# MEGA2560_Rev3e_0.net
KiCad netlist of a schematic drawn in Altium Designer
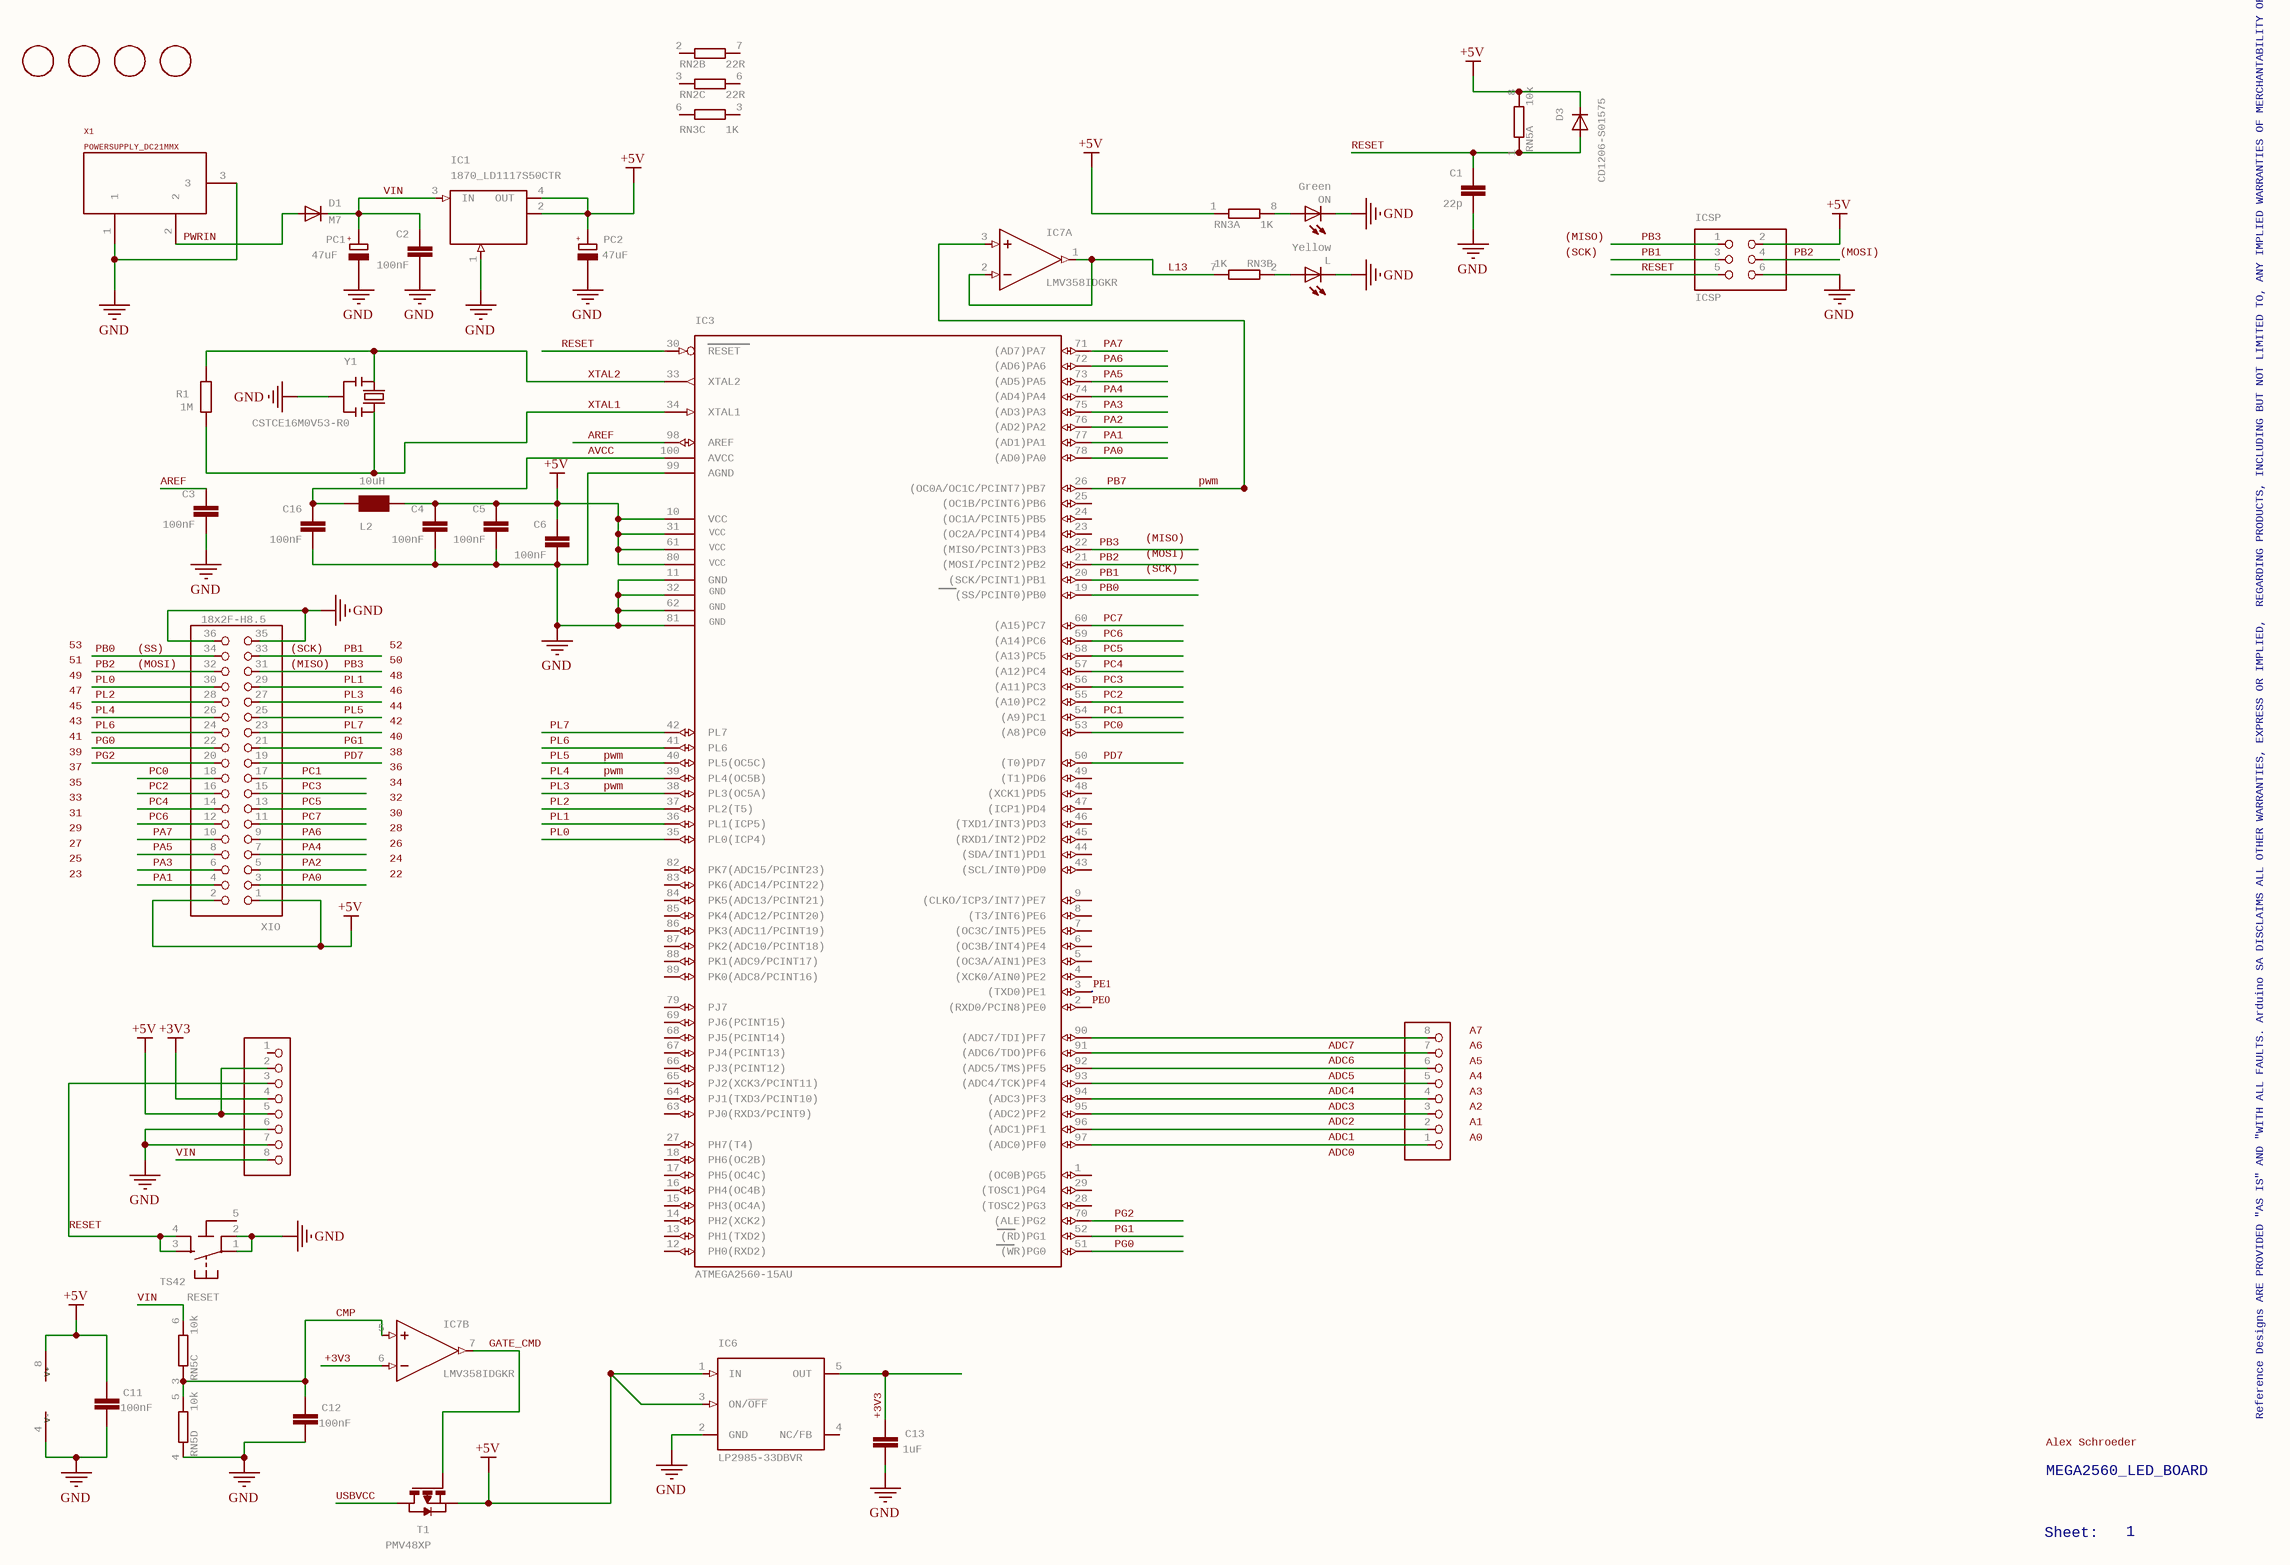
[diagram p0: MEGA2560_Rev3e_0.SchDoc]

(export (version "E")
  (design (tool "Eeschema 10.0.6"))
  (components
    (comp (ref "ADCL")
      (value "FH254-108DF08500V")
      (footprint "1X08")
      (description "Female Connector strip for Arduino bases - 8x1 F V h 8,5 p2,54mm")
      (fields (field (name "LIBRARYNAME") "Connettori"))
      (libsource (lib "Connettori") (part "0058_FH254-108DF08500V"))
    )
    (comp (ref "C1")
      (value "22p")
      (footprint "C0603-ROUND")
      (description "22pF 0603")
      (fields (field (name "PART_NUMBER") "22pF_0603"))
      (libsource (lib "Condensatori") (part "0014_22PF_0603"))
    )
    (comp (ref "C2")
      (value "100nF")
      (footprint "C0603-ROUND")
      (description "100nF 0603 50V")
      (fields (field (name "PART_NUMBER") "cl10b104kbnc"))
      (libsource (lib "Condensatori") (part "0015_100NF_0603"))
    )
    (comp (ref "C3")
      (value "100nF")
      (footprint "C0603-ROUND")
      (description "100nF 0603 50V")
      (fields (field (name "PART_NUMBER") "cl10b104kbnc"))
      (libsource (lib "Condensatori") (part "0015_100NF_0603"))
    )
    (comp (ref "C4")
      (value "100nF")
      (footprint "C0603-ROUND")
      (description "100nF 0603 50V")
      (fields (field (name "PART_NUMBER") "cl10b104kbnc"))
      (libsource (lib "Condensatori") (part "0015_100NF_0603"))
    )
    (comp (ref "C5")
      (value "100nF")
      (footprint "C0603-ROUND")
      (description "100nF 0603 50V")
      (fields (field (name "PART_NUMBER") "cl10b104kbnc"))
      (libsource (lib "Condensatori") (part "0015_100NF_0603"))
    )
    (comp (ref "C6")
      (value "100nF")
      (footprint "C0603-ROUND")
      (description "100nF 0603 50V")
      (fields (field (name "PART_NUMBER") "cl10b104kbnc"))
      (libsource (lib "Condensatori") (part "0015_100NF_0603"))
    )
    (comp (ref "C11")
      (value "100nF")
      (footprint "C0603-ROUND")
      (description "100nF 0603 50V")
      (fields (field (name "PART_NUMBER") "cl10b104kbnc"))
      (libsource (lib "") (part "0015_100NF_0603_1"))
    )
    (comp (ref "C12")
      (value "100nF")
      (footprint "C0603-ROUND")
      (description "100nF 0603 50V")
      (fields (field (name "PART_NUMBER") "cl10b104kbnc"))
      (libsource (lib "") (part "0015_100NF_0603_1"))
    )
    (comp (ref "C13")
      (value "1uF")
      (footprint "C0603-ROUND")
      (description "1uF 0603")
      (fields (field (name "PART_NUMBER") "1uF_0603/GRM188R61E105KA12D"))
      (libsource (lib "Condensatori") (part "0006_1UF_0603/GRM188R61E105KA12D"))
    )
    (comp (ref "C16")
      (value "100nF")
      (footprint "C0603-ROUND")
      (description "100nF 0603 50V")
      (fields (field (name "PART_NUMBER") "cl10b104kbnc"))
      (libsource (lib "Condensatori") (part "0015_100NF_0603"))
    )
    (comp (ref "D1")
      (value "M7")
      (footprint "SMB")
      (description "1.0A 40V SURFACE MOUNT GLASS PASSIVATED RECTIFIER   M7")
      (libsource (lib "Diodi") (part "0020_M7"))
    )
    (comp (ref "D3")
      (value "CD1206-S01575")
      (footprint "MINIMELF")
      (description "small-signal high-speed Switching Diodes   CD1206")
      (libsource (lib "Diodi") (part "0012_CD1206-S01575"))
    )
    (comp (ref "FD1")
      (value "FIDUCIALMOUNT")
      (footprint "FIDUCIA-MOUNT")
      (libsource (lib "SmartPrj") (part "FIDUCIALMOUNT"))
    )
    (comp (ref "FD2")
      (value "FIDUCIALMOUNT")
      (footprint "FIDUCIA-MOUNT")
      (libsource (lib "SmartPrj") (part "FIDUCIALMOUNT"))
    )
    (comp (ref "FD3")
      (value "FIDUCIALMOUNT")
      (footprint "FIDUCIA-MOUNT")
      (libsource (lib "SmartPrj") (part "FIDUCIALMOUNT"))
    )
    (comp (ref "FD4")
      (value "FIDUCIALMOUNT")
      (footprint "FIDUCIA-MOUNT")
      (libsource (lib "SmartPrj") (part "FIDUCIALMOUNT"))
    )
    (comp (ref "IC1")
      (value "1870_LD1117S50CTR")
      (footprint "LINEAR_SOT223")
      (description "Low-dropout linear regulator 5V  -LM1117IMPX-5.0")
      (fields (field (name "PART_NUMBER") "LD1117S50CTR"))
      (libsource (lib "IntegratedCircuits") (part "1870_LD1117S50CTR"))
    )
    (comp (ref "IC3")
      (value "ATMEGA2560-15AU")
      (footprint "TQFP100")
      (description "8-bit Microcontroller with 256K Bytes In-System Programmable Flash - ATMEGA2560-16AU")
      (fields
        (field (name "GND") "GND")
        (field (name "GND_1") "GND")
        (field (name "GND_2") "GND")
        (field (name "VCC") "VCC")
        (field (name "VCC_1") "VCC")
        (field (name "VCC_2") "VCC")
        (field (name "PART_NUMBER") "ATMEGA2560-16AU")
      )
      (libsource (lib "IntegratedCircuits") (part "0023_ATMEGA2560-16AU"))
    )
    (comp (ref "IC6")
      (value "LP2985-33DBVR")
      (footprint "SOT23-DBV")
      (description "150-mA LOW-NOISE LOW-DROPOUT REGULATOR WITH SHUTDOWN   LP2985-33DBVR")
      (fields (field (name "PART_NUMBER") "TEXLP2985-33DBVR"))
      (libsource (lib "IntegratedCircuits") (part "0008_TEXLP2985-33DBVR"))
    )
    (comp (ref "IC7")
      (value "LMV358IDGKR")
      (footprint "MSOP08")
      (fields (field (name "V+") "V+") (field (name "V-") "V-"))
      (libsource (lib "IntegratedCircuits") (part "0021_LMV358IDGKR"))
    )
    (comp (ref "ICSP")
      (value "ICSP")
      (footprint "2X03")
      (description "3x2 M V h 8,5 mm p2,54")
      (fields (field (name "PART_NUMBER") "PH254-203DF118A00V") (field (name "LIBRARYNAME") "Connettori"))
      (libsource (lib "Connettori") (part "0114_PH254-203DF118A00V"))
    )
    (comp (ref "L")
      (value "Yellow")
      (footprint "CHIPLED_0805")
      (description "LED YELLOW - SMD - 0805")
      (fields (field (name "PART_NUMBER") "KPT-2012YC"))
      (libsource (lib "Opto") (part "0044_KPT-2012YC"))
    )
    (comp (ref "L2")
      (value "10uH")
      (footprint "0805")
      (description "10uH 0805")
      (fields (field (name "PART_NUMBER") "CV201210-100K"))
      (libsource (lib "Induttanze") (part "0715_CV201210-100K"))
    )
    (comp (ref "ON")
      (value "Green")
      (footprint "CHIPLED_0805")
      (description "LED GREEN - SMD-0805")
      (fields (field (name "PART_NUMBER") "KPT-2012SGC"))
      (libsource (lib "Opto") (part "0043_KPT-2012SGC"))
    )
    (comp (ref "PC1")
      (value "47uF")
      (footprint "PANASONIC_D")
      (fields (field (name "+") "+"))
      (libsource (lib "Condensatori") (part "0113_47UF"))
    )
    (comp (ref "PC2")
      (value "47uF")
      (footprint "PANASONIC_D")
      (fields (field (name "+") "+"))
      (libsource (lib "Condensatori") (part "0113_47UF"))
    )
    (comp (ref "POWER")
      (value "FH254-108DF08500V")
      (footprint "1X08")
      (description "Female Connector strip for Arduino bases - 8x1 F V h 8,5 p2,54 serigrafato POWER")
      (fields (field (name "PART_NUMBER") "FH254-108DF08500T21") (field (name "LIBRARYNAME") "Connettori"))
      (libsource (lib "Connettori") (part "1217_FH254-108DF08500T21"))
    )
    (comp (ref "R1")
      (value "1M")
      (footprint "R0603-ROUND")
      (description "1M 0603")
      (fields (field (name "PART_NUMBER") "0603_1M") (field (name "LIBRARYNAME") "Resistenze"))
      (libsource (lib "Resistenze") (part "0004_0603_1M"))
    )
    (comp (ref "RESET")
      (value "TS42")
      (footprint "TS42")
      (description "Pushbutton 6x6 Smd - White")
      (fields (field (name "PART_NUMBER") "IT-1157AHNP-160G-G_GTR"))
      (libsource (lib "Switches") (part "0946_TS42031-160W-TR-7260"))
    )
    (comp (ref "RN2")
      (value "22R")
      (footprint "CAY16")
      (description "22R 064R")
      (fields
        (field (name "PART_NUMBER") "064R_22R_/_CAY16-220J4LF")
        (field (name "LIBRARYNAME") "Resistenze")
      )
      (libsource (lib "Resistenze") (part "0003_064R_22R_/_CAY16-220J4LF"))
    )
    (comp (ref "RN3")
      (value "1K")
      (footprint "CAY16")
      (description "1K 064R")
      (fields
        (field (name "PART_NUMBER") "064R_1K_/_CAY16-102J4LF")
        (field (name "LIBRARYNAME") "Resistenze")
      )
      (libsource (lib "Resistenze") (part "0005_064R_1K_/_CAY16-102J4LF"))
    )
    (comp (ref "RN5")
      (value "10k")
      (footprint "CAY16")
      (description "10K 064 R")
      (fields
        (field (name "PART_NUMBER") "064R_10K_/_CAY16-103J4LF")
        (field (name "LIBRARYNAME") "Resistenze")
      )
      (libsource (lib "Resistenze") (part "0016_064R_10K_/_CAY16-103J4LF"))
    )
    (comp (ref "T1")
      (value "PMV48XP")
      (footprint "SOT-23")
      (description "20 V, 3.5 A P-channel Trench MOSFET - PMV48XP")
      (libsource (lib "Transistors") (part "0297_PMV48XP"))
    )
    (comp (ref "X1")
      (value "POWERSUPPLY_DC21MMX")
      (footprint "POWERSUPPLY_DC-21MM")
      (libsource (lib "SmartPrj") (part "POWERSUPPLY_DC21MMX"))
    )
    (comp (ref "XIO")
      (value "18x2F-H8.5")
      (footprint "2X18")
      (description "18x2 F V h 8,5 p2,54")
      (fields (field (name "PART_NUMBER") "FH254-218DF08500V") (field (name "LIBRARYNAME") "Connettori"))
      (libsource (lib "Connettori") (part "0060_FH254-218DF08500V"))
    )
    (comp (ref "Y1")
      (value "CSTCE16M0V53-R0")
      (footprint "RESONATOR")
      (description "16Mhz - SMD")
      (fields (field (name "LIBRARYNAME") "Cristalli"))
      (libsource (lib "Cristalli") (part "0011_CSTCE16M0V53-R0"))
    )
  )
  (nets
    (net (code "1") (name "+3V3") (class "Default")
      (node (ref "C13") (pin "2") (pinfunction "2_2") (pintype "passive"))
      (node (ref "IC6") (pin "5") (pinfunction "OUT_5") (pintype "passive"))
      (node (ref "IC7") (pin "6") (pinfunction "-IN_6") (pintype "input"))
      (node (ref "POWER") (pin "4") (pinfunction "4_4") (pintype "passive"))
    )
    (net (code "2") (name "+5V") (class "Default")
      (node (ref "C11") (pin "2") (pinfunction "2_2") (pintype "passive"))
      (node (ref "C4") (pin "1") (pinfunction "1_1") (pintype "passive"))
      (node (ref "C5") (pin "1") (pinfunction "1_1") (pintype "passive"))
      (node (ref "C6") (pin "1") (pinfunction "1_1") (pintype "passive"))
      (node (ref "D3") (pin "C") (pinfunction "C_C") (pintype "passive"))
      (node (ref "IC1") (pin "2") (pinfunction "OUT_2") (pintype "passive"))
      (node (ref "IC1") (pin "4") (pinfunction "OUT_4") (pintype "passive"))
      (node (ref "IC3") (pin "10") (pinfunction "VCC_10") (pintype "power_in"))
      (node (ref "IC3") (pin "31") (pinfunction "VCC1_31") (pintype "power_in"))
      (node (ref "IC3") (pin "61") (pinfunction "VCC2_61") (pintype "power_in"))
      (node (ref "IC3") (pin "80") (pinfunction "VCC3_80") (pintype "power_in"))
      (node (ref "IC6") (pin "1") (pinfunction "IN_1") (pintype "input"))
      (node (ref "IC6") (pin "3") (pinfunction "ON/~{OFF}_3") (pintype "input"))
      (node (ref "IC7") (pin "8") (pinfunction "V+_8") (pintype "power_in"))
      (node (ref "ICSP") (pin "2") (pinfunction "2_2") (pintype "passive"))
      (node (ref "L2") (pin "2") (pinfunction "2_2") (pintype "passive"))
      (node (ref "PC2") (pin "+") (pinfunction "+_+") (pintype "passive"))
      (node (ref "POWER") (pin "2") (pinfunction "2_2") (pintype "passive"))
      (node (ref "POWER") (pin "5") (pinfunction "5_5") (pintype "passive"))
      (node (ref "RN3") (pin "1") (pinfunction "1_1") (pintype "passive"))
      (node (ref "RN5") (pin "8") (pinfunction "2_8") (pintype "passive"))
      (node (ref "T1") (pin "2") (pinfunction "S_2") (pintype "passive"))
      (node (ref "XIO") (pin "1") (pinfunction "1_1") (pintype "passive"))
      (node (ref "XIO") (pin "2") (pinfunction "2_2") (pintype "passive"))
    )
    (net (code "3") (name "/ADC0") (class "Default")
      (node (ref "ADCL") (pin "1") (pinfunction "1_1") (pintype "passive"))
      (node (ref "IC3") (pin "97") (pinfunction "(ADC0)PF0_97") (pintype "bidirectional"))
    )
    (net (code "4") (name "/ADC1") (class "Default")
      (node (ref "ADCL") (pin "2") (pinfunction "2_2") (pintype "passive"))
      (node (ref "IC3") (pin "96") (pinfunction "(ADC1)PF1_96") (pintype "bidirectional"))
    )
    (net (code "5") (name "/ADC2") (class "Default")
      (node (ref "ADCL") (pin "3") (pinfunction "3_3") (pintype "passive"))
      (node (ref "IC3") (pin "95") (pinfunction "(ADC2)PF2_95") (pintype "bidirectional"))
    )
    (net (code "6") (name "/ADC3") (class "Default")
      (node (ref "ADCL") (pin "4") (pinfunction "4_4") (pintype "passive"))
      (node (ref "IC3") (pin "94") (pinfunction "(ADC3)PF3_94") (pintype "bidirectional"))
    )
    (net (code "7") (name "/ADC4") (class "Default")
      (node (ref "ADCL") (pin "5") (pinfunction "5_5") (pintype "passive"))
      (node (ref "IC3") (pin "93") (pinfunction "(ADC4/TCK)PF4_93") (pintype "bidirectional"))
    )
    (net (code "8") (name "/ADC5") (class "Default")
      (node (ref "ADCL") (pin "6") (pinfunction "6_6") (pintype "passive"))
      (node (ref "IC3") (pin "92") (pinfunction "(ADC5/TMS)PF5_92") (pintype "bidirectional"))
    )
    (net (code "9") (name "/ADC6") (class "Default")
      (node (ref "ADCL") (pin "7") (pinfunction "7_7") (pintype "passive"))
      (node (ref "IC3") (pin "91") (pinfunction "(ADC6/TDO)PF6_91") (pintype "bidirectional"))
    )
    (net (code "10") (name "/ADC7") (class "Default")
      (node (ref "ADCL") (pin "8") (pinfunction "8_8") (pintype "passive"))
      (node (ref "IC3") (pin "90") (pinfunction "(ADC7/TDI)PF7_90") (pintype "bidirectional"))
    )
    (net (code "11") (name "/AREF") (class "Default")
      (node (ref "C3") (pin "1") (pinfunction "1_1") (pintype "passive"))
      (node (ref "IC3") (pin "98") (pinfunction "AREF_98") (pintype "bidirectional"))
    )
    (net (code "12") (name "/AVCC") (class "Default")
      (node (ref "C16") (pin "1") (pinfunction "1_1") (pintype "passive"))
      (node (ref "IC3") (pin "100") (pinfunction "AVCC_100") (pintype "power_in"))
      (node (ref "L2") (pin "1") (pinfunction "1_1") (pintype "passive"))
    )
    (net (code "13") (name "/CMP") (class "Default")
      (node (ref "C12") (pin "2") (pinfunction "2_2") (pintype "passive"))
      (node (ref "IC7") (pin "5") (pinfunction "+IN_5") (pintype "input"))
      (node (ref "RN5") (pin "3") (pinfunction "1_3") (pintype "passive"))
      (node (ref "RN5") (pin "5") (pinfunction "2_5") (pintype "passive"))
    )
    (net (code "14") (name "/GATE_CMD") (class "Default")
      (node (ref "IC7") (pin "7") (pinfunction "OUT_7") (pintype "output"))
      (node (ref "T1") (pin "3") (pinfunction "G_3") (pintype "passive"))
    )
    (net (code "15") (name "/L13") (class "Default")
      (node (ref "IC7") (pin "1") (pinfunction "OUT_1") (pintype "output"))
      (node (ref "IC7") (pin "2") (pinfunction "-IN_2") (pintype "input"))
      (node (ref "RN3") (pin "7") (pinfunction "2_7") (pintype "passive"))
    )
    (net (code "16") (name "/PA0") (class "Default")
      (node (ref "IC3") (pin "78") (pinfunction "(AD0)PA0_78") (pintype "bidirectional"))
      (node (ref "XIO") (pin "3") (pinfunction "3_3") (pintype "passive"))
    )
    (net (code "17") (name "/PA1") (class "Default")
      (node (ref "IC3") (pin "77") (pinfunction "(AD1)PA1_77") (pintype "bidirectional"))
      (node (ref "XIO") (pin "4") (pinfunction "4_4") (pintype "passive"))
    )
    (net (code "18") (name "/PA2") (class "Default")
      (node (ref "IC3") (pin "76") (pinfunction "(AD2)PA2_76") (pintype "bidirectional"))
      (node (ref "XIO") (pin "5") (pinfunction "5_5") (pintype "passive"))
    )
    (net (code "19") (name "/PA3") (class "Default")
      (node (ref "IC3") (pin "75") (pinfunction "(AD3)PA3_75") (pintype "bidirectional"))
      (node (ref "XIO") (pin "6") (pinfunction "6_6") (pintype "passive"))
    )
    (net (code "20") (name "/PA4") (class "Default")
      (node (ref "IC3") (pin "74") (pinfunction "(AD4)PA4_74") (pintype "bidirectional"))
      (node (ref "XIO") (pin "7") (pinfunction "7_7") (pintype "passive"))
    )
    (net (code "21") (name "/PA5") (class "Default")
      (node (ref "IC3") (pin "73") (pinfunction "(AD5)PA5_73") (pintype "bidirectional"))
      (node (ref "XIO") (pin "8") (pinfunction "8_8") (pintype "passive"))
    )
    (net (code "22") (name "/PA6") (class "Default")
      (node (ref "IC3") (pin "72") (pinfunction "(AD6)PA6_72") (pintype "bidirectional"))
      (node (ref "XIO") (pin "9") (pinfunction "9_9") (pintype "passive"))
    )
    (net (code "23") (name "/PA7") (class "Default")
      (node (ref "IC3") (pin "71") (pinfunction "(AD7)PA7_71") (pintype "bidirectional"))
      (node (ref "XIO") (pin "10") (pinfunction "10_10") (pintype "passive"))
    )
    (net (code "24") (name "/PB0") (class "Default")
      (node (ref "IC3") (pin "19") (pinfunction "(SS/PCINT0)PB0_19") (pintype "bidirectional"))
      (node (ref "XIO") (pin "34") (pinfunction "34_34") (pintype "passive"))
    )
    (net (code "25") (name "/PB1") (class "Default")
      (node (ref "IC3") (pin "20") (pinfunction "(SCK/PCINT1)PB1_20") (pintype "bidirectional"))
      (node (ref "ICSP") (pin "3") (pinfunction "3_3") (pintype "passive"))
      (node (ref "XIO") (pin "33") (pinfunction "33_33") (pintype "passive"))
    )
    (net (code "26") (name "/PB2") (class "Default")
      (node (ref "IC3") (pin "21") (pinfunction "(MOSI/PCINT2)PB2_21") (pintype "bidirectional"))
      (node (ref "ICSP") (pin "4") (pinfunction "4_4") (pintype "passive"))
      (node (ref "XIO") (pin "32") (pinfunction "32_32") (pintype "passive"))
    )
    (net (code "27") (name "/PB3") (class "Default")
      (node (ref "IC3") (pin "22") (pinfunction "(MISO/PCINT3)PB3_22") (pintype "bidirectional"))
      (node (ref "ICSP") (pin "1") (pinfunction "1_1") (pintype "passive"))
      (node (ref "XIO") (pin "31") (pinfunction "31_31") (pintype "passive"))
    )
    (net (code "28") (name "/PB7") (class "Default")
      (node (ref "IC3") (pin "26") (pinfunction "(OC0A/OC1C/PCINT7)PB7_26") (pintype "bidirectional"))
      (node (ref "IC7") (pin "3") (pinfunction "+IN_3") (pintype "input"))
    )
    (net (code "29") (name "/PC0") (class "Default")
      (node (ref "IC3") (pin "53") (pinfunction "(A8)PC0_53") (pintype "bidirectional"))
      (node (ref "XIO") (pin "18") (pinfunction "18_18") (pintype "passive"))
    )
    (net (code "30") (name "/PC1") (class "Default")
      (node (ref "IC3") (pin "54") (pinfunction "(A9)PC1_54") (pintype "bidirectional"))
      (node (ref "XIO") (pin "17") (pinfunction "17_17") (pintype "passive"))
    )
    (net (code "31") (name "/PC2") (class "Default")
      (node (ref "IC3") (pin "55") (pinfunction "(A10)PC2_55") (pintype "bidirectional"))
      (node (ref "XIO") (pin "16") (pinfunction "16_16") (pintype "passive"))
    )
    (net (code "32") (name "/PC3") (class "Default")
      (node (ref "IC3") (pin "56") (pinfunction "(A11)PC3_56") (pintype "bidirectional"))
      (node (ref "XIO") (pin "15") (pinfunction "15_15") (pintype "passive"))
    )
    (net (code "33") (name "/PC4") (class "Default")
      (node (ref "IC3") (pin "57") (pinfunction "(A12)PC4_57") (pintype "bidirectional"))
      (node (ref "XIO") (pin "14") (pinfunction "14_14") (pintype "passive"))
    )
    (net (code "34") (name "/PC5") (class "Default")
      (node (ref "IC3") (pin "58") (pinfunction "(A13)PC5_58") (pintype "bidirectional"))
      (node (ref "XIO") (pin "13") (pinfunction "13_13") (pintype "passive"))
    )
    (net (code "35") (name "/PC6") (class "Default")
      (node (ref "IC3") (pin "59") (pinfunction "(A14)PC6_59") (pintype "bidirectional"))
      (node (ref "XIO") (pin "12") (pinfunction "12_12") (pintype "passive"))
    )
    (net (code "36") (name "/PC7") (class "Default")
      (node (ref "IC3") (pin "60") (pinfunction "(A15)PC7_60") (pintype "bidirectional"))
      (node (ref "XIO") (pin "11") (pinfunction "11_11") (pintype "passive"))
    )
    (net (code "37") (name "/PD7") (class "Default")
      (node (ref "IC3") (pin "50") (pinfunction "(T0)PD7_50") (pintype "bidirectional"))
      (node (ref "XIO") (pin "19") (pinfunction "19_19") (pintype "passive"))
    )
    (net (code "38") (name "/PE0") (class "Default")
      (node (ref "IC3") (pin "2") (pinfunction "(RXD0/PCIN8)PE0_2") (pintype "bidirectional"))
    )
    (net (code "39") (name "/PE1") (class "Default")
      (node (ref "IC3") (pin "3") (pinfunction "(TXD0)PE1_3") (pintype "bidirectional"))
    )
    (net (code "40") (name "/PG0") (class "Default")
      (node (ref "IC3") (pin "51") (pinfunction "(WR)PG0_51") (pintype "bidirectional"))
      (node (ref "XIO") (pin "22") (pinfunction "22_22") (pintype "passive"))
    )
    (net (code "41") (name "/PG1") (class "Default")
      (node (ref "IC3") (pin "52") (pinfunction "(RD)PG1_52") (pintype "bidirectional"))
      (node (ref "XIO") (pin "21") (pinfunction "21_21") (pintype "passive"))
    )
    (net (code "42") (name "/PG2") (class "Default")
      (node (ref "IC3") (pin "70") (pinfunction "(ALE)PG2_70") (pintype "bidirectional"))
      (node (ref "XIO") (pin "20") (pinfunction "20_20") (pintype "passive"))
    )
    (net (code "43") (name "/PL0") (class "Default")
      (node (ref "IC3") (pin "35") (pinfunction "PL0(ICP4)_35") (pintype "bidirectional"))
      (node (ref "XIO") (pin "30") (pinfunction "30_30") (pintype "passive"))
    )
    (net (code "44") (name "/PL1") (class "Default")
      (node (ref "IC3") (pin "36") (pinfunction "PL1(ICP5)_36") (pintype "bidirectional"))
      (node (ref "XIO") (pin "29") (pinfunction "29_29") (pintype "passive"))
    )
    (net (code "45") (name "/PL2") (class "Default")
      (node (ref "IC3") (pin "37") (pinfunction "PL2(T5)_37") (pintype "bidirectional"))
      (node (ref "XIO") (pin "28") (pinfunction "28_28") (pintype "passive"))
    )
    (net (code "46") (name "/PL3") (class "Default")
      (node (ref "IC3") (pin "38") (pinfunction "PL3(OC5A)_38") (pintype "bidirectional"))
      (node (ref "XIO") (pin "27") (pinfunction "27_27") (pintype "passive"))
    )
    (net (code "47") (name "/PL4") (class "Default")
      (node (ref "IC3") (pin "39") (pinfunction "PL4(OC5B)_39") (pintype "bidirectional"))
      (node (ref "XIO") (pin "26") (pinfunction "26_26") (pintype "passive"))
    )
    (net (code "48") (name "/PL5") (class "Default")
      (node (ref "IC3") (pin "40") (pinfunction "PL5(OC5C)_40") (pintype "bidirectional"))
      (node (ref "XIO") (pin "25") (pinfunction "25_25") (pintype "passive"))
    )
    (net (code "49") (name "/PL6") (class "Default")
      (node (ref "IC3") (pin "41") (pinfunction "PL6_41") (pintype "bidirectional"))
      (node (ref "XIO") (pin "24") (pinfunction "24_24") (pintype "passive"))
    )
    (net (code "50") (name "/PL7") (class "Default")
      (node (ref "IC3") (pin "42") (pinfunction "PL7_42") (pintype "bidirectional"))
      (node (ref "XIO") (pin "23") (pinfunction "23_23") (pintype "passive"))
    )
    (net (code "51") (name "/PWRIN") (class "Default")
      (node (ref "D1") (pin "A") (pinfunction "A_A") (pintype "passive"))
      (node (ref "X1") (pin "2") (pinfunction "2_2") (pintype "power_in"))
    )
    (net (code "52") (name "/RESET") (class "Default")
      (node (ref "C1") (pin "1") (pinfunction "1_1") (pintype "passive"))
      (node (ref "D3") (pin "A") (pinfunction "A_A") (pintype "passive"))
      (node (ref "IC3") (pin "30") (pinfunction "RESET_30") (pintype "input"))
      (node (ref "ICSP") (pin "5") (pinfunction "5_5") (pintype "passive"))
      (node (ref "POWER") (pin "3") (pinfunction "3_3") (pintype "passive"))
      (node (ref "RESET") (pin "3") (pinfunction "3_3") (pintype "passive"))
      (node (ref "RESET") (pin "4") (pinfunction "4_4") (pintype "passive"))
      (node (ref "RN5") (pin "1") (pinfunction "1_1") (pintype "passive"))
    )
    (net (code "53") (name "/USBVCC") (class "Default")
      (node (ref "T1") (pin "1") (pinfunction "D_1") (pintype "passive"))
    )
    (net (code "54") (name "/VIN") (class "Default")
      (node (ref "C2") (pin "1") (pinfunction "1_1") (pintype "passive"))
      (node (ref "D1") (pin "C") (pinfunction "C_C") (pintype "passive"))
      (node (ref "IC1") (pin "3") (pinfunction "IN_3") (pintype "input"))
      (node (ref "PC1") (pin "+") (pinfunction "+_+") (pintype "passive"))
      (node (ref "POWER") (pin "8") (pinfunction "8_8") (pintype "passive"))
      (node (ref "RN5") (pin "6") (pinfunction "2_6") (pintype "passive"))
    )
    (net (code "55") (name "/XTAL1") (class "Default")
      (node (ref "IC3") (pin "34") (pinfunction "XTAL1_34") (pintype "input"))
      (node (ref "R1") (pin "1") (pinfunction "1_1") (pintype "passive"))
      (node (ref "Y1") (pin "3") (pinfunction "3_3") (pintype "passive"))
    )
    (net (code "56") (name "/XTAL2") (class "Default")
      (node (ref "IC3") (pin "33") (pinfunction "XTAL2_33") (pintype "output"))
      (node (ref "R1") (pin "2") (pinfunction "2_2") (pintype "passive"))
      (node (ref "Y1") (pin "1") (pinfunction "1_1") (pintype "passive"))
    )
    (net (code "57") (name "GND") (class "Default")
      (node (ref "C1") (pin "2") (pinfunction "2_2") (pintype "passive"))
      (node (ref "C11") (pin "1") (pinfunction "1_1") (pintype "passive"))
      (node (ref "C12") (pin "1") (pinfunction "1_1") (pintype "passive"))
      (node (ref "C13") (pin "1") (pinfunction "1_1") (pintype "passive"))
      (node (ref "C16") (pin "2") (pinfunction "2_2") (pintype "passive"))
      (node (ref "C2") (pin "2") (pinfunction "2_2") (pintype "passive"))
      (node (ref "C3") (pin "2") (pinfunction "2_2") (pintype "passive"))
      (node (ref "C4") (pin "2") (pinfunction "2_2") (pintype "passive"))
      (node (ref "C5") (pin "2") (pinfunction "2_2") (pintype "passive"))
      (node (ref "C6") (pin "2") (pinfunction "2_2") (pintype "passive"))
      (node (ref "IC1") (pin "1") (pinfunction "GND/ADJ_1") (pintype "input"))
      (node (ref "IC3") (pin "11") (pinfunction "GND_11") (pintype "power_in"))
      (node (ref "IC3") (pin "32") (pinfunction "GND1_32") (pintype "power_in"))
      (node (ref "IC3") (pin "62") (pinfunction "GND2_62") (pintype "power_in"))
      (node (ref "IC3") (pin "81") (pinfunction "GND3_81") (pintype "power_in"))
      (node (ref "IC3") (pin "99") (pinfunction "AGND_99") (pintype "power_in"))
      (node (ref "IC6") (pin "2") (pinfunction "GND_2") (pintype "power_in"))
      (node (ref "IC7") (pin "4") (pinfunction "V-_4") (pintype "power_in"))
      (node (ref "ICSP") (pin "6") (pinfunction "6_6") (pintype "passive"))
      (node (ref "L") (pin "C") (pinfunction "C_C") (pintype "passive"))
      (node (ref "ON") (pin "C") (pinfunction "C_C") (pintype "passive"))
      (node (ref "PC1") (pin "-") (pinfunction "-_-") (pintype "passive"))
      (node (ref "PC2") (pin "-") (pinfunction "-_-") (pintype "passive"))
      (node (ref "POWER") (pin "6") (pinfunction "6_6") (pintype "passive"))
      (node (ref "POWER") (pin "7") (pinfunction "7_7") (pintype "passive"))
      (node (ref "RESET") (pin "1") (pinfunction "1_1") (pintype "passive"))
      (node (ref "RESET") (pin "2") (pinfunction "2_2") (pintype "passive"))
      (node (ref "RN5") (pin "4") (pinfunction "1_4") (pintype "passive"))
      (node (ref "X1") (pin "1") (pinfunction "1_1") (pintype "power_in"))
      (node (ref "X1") (pin "3") (pinfunction "3_3") (pintype "power_in"))
      (node (ref "XIO") (pin "35") (pinfunction "35_35") (pintype "passive"))
      (node (ref "XIO") (pin "36") (pinfunction "36_36") (pintype "passive"))
      (node (ref "Y1") (pin "2") (pinfunction "2_2") (pintype "passive"))
    )
    (net (code "58") (name "Net-(RN3A-2)") (class "Default")
      (node (ref "ON") (pin "A") (pinfunction "A_A") (pintype "passive"))
      (node (ref "RN3") (pin "8") (pinfunction "2_8") (pintype "passive"))
    )
    (net (code "59") (name "Net-(RN3B-1)") (class "Default")
      (node (ref "L") (pin "A") (pinfunction "A_A") (pintype "passive"))
      (node (ref "RN3") (pin "2") (pinfunction "1_2") (pintype "passive"))
    )
    (net (code "60") (name "unconnected-(IC3-(CLKO{slash}ICP3{slash}INT7)PE7-Pad9)") (class "Default")
      (node (ref "IC3") (pin "9") (pinfunction "(CLKO/ICP3/INT7)PE7_9") (pintype "bidirectional"))
    )
    (net (code "61") (name "unconnected-(IC3-(ICP1)PD4-Pad47)") (class "Default")
      (node (ref "IC3") (pin "47") (pinfunction "(ICP1)PD4_47") (pintype "bidirectional"))
    )
    (net (code "62") (name "unconnected-(IC3-(OC0B)PG5-Pad1)") (class "Default")
      (node (ref "IC3") (pin "1") (pinfunction "(OC0B)PG5_1") (pintype "bidirectional"))
    )
    (net (code "63") (name "unconnected-(IC3-(OC1A{slash}PCINT5)PB5-Pad24)") (class "Default")
      (node (ref "IC3") (pin "24") (pinfunction "(OC1A/PCINT5)PB5_24") (pintype "bidirectional"))
    )
    (net (code "64") (name "unconnected-(IC3-(OC1B{slash}PCINT6)PB6-Pad25)") (class "Default")
      (node (ref "IC3") (pin "25") (pinfunction "(OC1B/PCINT6)PB6_25") (pintype "bidirectional"))
    )
    (net (code "65") (name "unconnected-(IC3-(OC2A{slash}PCINT4)PB4-Pad23)") (class "Default")
      (node (ref "IC3") (pin "23") (pinfunction "(OC2A/PCINT4)PB4_23") (pintype "bidirectional"))
    )
    (net (code "66") (name "unconnected-(IC3-(OC3A{slash}AIN1)PE3-Pad5)") (class "Default")
      (node (ref "IC3") (pin "5") (pinfunction "(OC3A/AIN1)PE3_5") (pintype "bidirectional"))
    )
    (net (code "67") (name "unconnected-(IC3-(OC3B{slash}INT4)PE4-Pad6)") (class "Default")
      (node (ref "IC3") (pin "6") (pinfunction "(OC3B/INT4)PE4_6") (pintype "bidirectional"))
    )
    (net (code "68") (name "unconnected-(IC3-(OC3C{slash}INT5)PE5-Pad7)") (class "Default")
      (node (ref "IC3") (pin "7") (pinfunction "(OC3C/INT5)PE5_7") (pintype "bidirectional"))
    )
    (net (code "69") (name "unconnected-(IC3-(RXD1{slash}INT2)PD2-Pad45)") (class "Default")
      (node (ref "IC3") (pin "45") (pinfunction "(RXD1/INT2)PD2_45") (pintype "bidirectional"))
    )
    (net (code "70") (name "unconnected-(IC3-(SCL{slash}INT0)PD0-Pad43)") (class "Default")
      (node (ref "IC3") (pin "43") (pinfunction "(SCL/INT0)PD0_43") (pintype "bidirectional"))
    )
    (net (code "71") (name "unconnected-(IC3-(SDA{slash}INT1)PD1-Pad44)") (class "Default")
      (node (ref "IC3") (pin "44") (pinfunction "(SDA/INT1)PD1_44") (pintype "bidirectional"))
    )
    (net (code "72") (name "unconnected-(IC3-(T1)PD6-Pad49)") (class "Default")
      (node (ref "IC3") (pin "49") (pinfunction "(T1)PD6_49") (pintype "bidirectional"))
    )
    (net (code "73") (name "unconnected-(IC3-(T3{slash}INT6)PE6-Pad8)") (class "Default")
      (node (ref "IC3") (pin "8") (pinfunction "(T3/INT6)PE6_8") (pintype "bidirectional"))
    )
    (net (code "74") (name "unconnected-(IC3-(TOSC1)PG4-Pad29)") (class "Default")
      (node (ref "IC3") (pin "29") (pinfunction "(TOSC1)PG4_29") (pintype "bidirectional"))
    )
    (net (code "75") (name "unconnected-(IC3-(TOSC2)PG3-Pad28)") (class "Default")
      (node (ref "IC3") (pin "28") (pinfunction "(TOSC2)PG3_28") (pintype "bidirectional"))
    )
    (net (code "76") (name "unconnected-(IC3-(TXD1{slash}INT3)PD3-Pad46)") (class "Default")
      (node (ref "IC3") (pin "46") (pinfunction "(TXD1/INT3)PD3_46") (pintype "bidirectional"))
    )
    (net (code "77") (name "unconnected-(IC3-(XCK0{slash}AIN0)PE2-Pad4)") (class "Default")
      (node (ref "IC3") (pin "4") (pinfunction "(XCK0/AIN0)PE2_4") (pintype "bidirectional"))
    )
    (net (code "78") (name "unconnected-(IC3-(XCK1)PD5-Pad48)") (class "Default")
      (node (ref "IC3") (pin "48") (pinfunction "(XCK1)PD5_48") (pintype "bidirectional"))
    )
    (net (code "79") (name "unconnected-(IC3-PH0(RXD2)-Pad12)") (class "Default")
      (node (ref "IC3") (pin "12") (pinfunction "PH0(RXD2)_12") (pintype "bidirectional"))
    )
    (net (code "80") (name "unconnected-(IC3-PH1(TXD2)-Pad13)") (class "Default")
      (node (ref "IC3") (pin "13") (pinfunction "PH1(TXD2)_13") (pintype "bidirectional"))
    )
    (net (code "81") (name "unconnected-(IC3-PH2(XCK2)-Pad14)") (class "Default")
      (node (ref "IC3") (pin "14") (pinfunction "PH2(XCK2)_14") (pintype "bidirectional"))
    )
    (net (code "82") (name "unconnected-(IC3-PH3(OC4A)-Pad15)") (class "Default")
      (node (ref "IC3") (pin "15") (pinfunction "PH3(OC4A)_15") (pintype "bidirectional"))
    )
    (net (code "83") (name "unconnected-(IC3-PH4(OC4B)-Pad16)") (class "Default")
      (node (ref "IC3") (pin "16") (pinfunction "PH4(OC4B)_16") (pintype "bidirectional"))
    )
    (net (code "84") (name "unconnected-(IC3-PH5(OC4C)-Pad17)") (class "Default")
      (node (ref "IC3") (pin "17") (pinfunction "PH5(OC4C)_17") (pintype "bidirectional"))
    )
    (net (code "85") (name "unconnected-(IC3-PH6(OC2B)-Pad18)") (class "Default")
      (node (ref "IC3") (pin "18") (pinfunction "PH6(OC2B)_18") (pintype "bidirectional"))
    )
    (net (code "86") (name "unconnected-(IC3-PH7(T4)-Pad27)") (class "Default")
      (node (ref "IC3") (pin "27") (pinfunction "PH7(T4)_27") (pintype "bidirectional"))
    )
    (net (code "87") (name "unconnected-(IC3-PJ0(RXD3{slash}PCINT9)-Pad63)") (class "Default")
      (node (ref "IC3") (pin "63") (pinfunction "PJ0(RXD3/PCINT9)_63") (pintype "bidirectional"))
    )
    (net (code "88") (name "unconnected-(IC3-PJ1(TXD3{slash}PCINT10)-Pad64)") (class "Default")
      (node (ref "IC3") (pin "64") (pinfunction "PJ1(TXD3/PCINT10)_64") (pintype "bidirectional"))
    )
    (net (code "89") (name "unconnected-(IC3-PJ2(XCK3{slash}PCINT11)-Pad65)") (class "Default")
      (node (ref "IC3") (pin "65") (pinfunction "PJ2(XCK3/PCINT11)_65") (pintype "bidirectional"))
    )
    (net (code "90") (name "unconnected-(IC3-PJ3(PCINT12)-Pad66)") (class "Default")
      (node (ref "IC3") (pin "66") (pinfunction "PJ3(PCINT12)_66") (pintype "bidirectional"))
    )
    (net (code "91") (name "unconnected-(IC3-PJ4(PCINT13)-Pad67)") (class "Default")
      (node (ref "IC3") (pin "67") (pinfunction "PJ4(PCINT13)_67") (pintype "bidirectional"))
    )
    (net (code "92") (name "unconnected-(IC3-PJ5(PCINT14)-Pad68)") (class "Default")
      (node (ref "IC3") (pin "68") (pinfunction "PJ5(PCINT14)_68") (pintype "bidirectional"))
    )
    (net (code "93") (name "unconnected-(IC3-PJ6(PCINT15)-Pad69)") (class "Default")
      (node (ref "IC3") (pin "69") (pinfunction "PJ6(PCINT15)_69") (pintype "bidirectional"))
    )
    (net (code "94") (name "unconnected-(IC3-PJ7-Pad79)") (class "Default")
      (node (ref "IC3") (pin "79") (pinfunction "PJ7_79") (pintype "bidirectional"))
    )
    (net (code "95") (name "unconnected-(IC3-PK0(ADC8{slash}PCINT16)-Pad89)") (class "Default")
      (node (ref "IC3") (pin "89") (pinfunction "PK0(ADC8/PCINT16)_89") (pintype "bidirectional"))
    )
    (net (code "96") (name "unconnected-(IC3-PK1(ADC9{slash}PCINT17)-Pad88)") (class "Default")
      (node (ref "IC3") (pin "88") (pinfunction "PK1(ADC9/PCINT17)_88") (pintype "bidirectional"))
    )
    (net (code "97") (name "unconnected-(IC3-PK2(ADC10{slash}PCINT18)-Pad87)") (class "Default")
      (node (ref "IC3") (pin "87") (pinfunction "PK2(ADC10/PCINT18)_87") (pintype "bidirectional"))
    )
    (net (code "98") (name "unconnected-(IC3-PK3(ADC11{slash}PCINT19)-Pad86)") (class "Default")
      (node (ref "IC3") (pin "86") (pinfunction "PK3(ADC11/PCINT19)_86") (pintype "bidirectional"))
    )
    (net (code "99") (name "unconnected-(IC3-PK4(ADC12{slash}PCINT20)-Pad85)") (class "Default")
      (node (ref "IC3") (pin "85") (pinfunction "PK4(ADC12/PCINT20)_85") (pintype "bidirectional"))
    )
    (net (code "100") (name "unconnected-(IC3-PK5(ADC13{slash}PCINT21)-Pad84)") (class "Default")
      (node (ref "IC3") (pin "84") (pinfunction "PK5(ADC13/PCINT21)_84") (pintype "bidirectional"))
    )
    (net (code "101") (name "unconnected-(IC3-PK6(ADC14{slash}PCINT22)-Pad83)") (class "Default")
      (node (ref "IC3") (pin "83") (pinfunction "PK6(ADC14/PCINT22)_83") (pintype "bidirectional"))
    )
    (net (code "102") (name "unconnected-(IC3-PK7(ADC15{slash}PCINT23)-Pad82)") (class "Default")
      (node (ref "IC3") (pin "82") (pinfunction "PK7(ADC15/PCINT23)_82") (pintype "bidirectional"))
    )
    (net (code "103") (name "unconnected-(IC6-NC{slash}FB-Pad4)") (class "Default")
      (node (ref "IC6") (pin "4") (pinfunction "NC/FB_4") (pintype "passive"))
    )
    (net (code "104") (name "unconnected-(POWER-Pad1)") (class "Default")
      (node (ref "POWER") (pin "1") (pinfunction "1_1") (pintype "passive"))
    )
    (net (code "105") (name "unconnected-(RESET-5-GND-Pad5)") (class "Default")
      (node (ref "RESET") (pin "5") (pinfunction "5-GND_5") (pintype "power_in"))
    )
    (net (code "106") (name "unconnected-(RN2B-1-Pad2)") (class "Default")
      (node (ref "RN2") (pin "2") (pinfunction "1_2") (pintype "passive"))
    )
    (net (code "107") (name "unconnected-(RN2B-2-Pad7)") (class "Default")
      (node (ref "RN2") (pin "7") (pinfunction "2_7") (pintype "passive"))
    )
    (net (code "108") (name "unconnected-(RN2C-1-Pad3)") (class "Default")
      (node (ref "RN2") (pin "3") (pinfunction "1_3") (pintype "passive"))
    )
    (net (code "109") (name "unconnected-(RN2C-2-Pad6)") (class "Default")
      (node (ref "RN2") (pin "6") (pinfunction "2_6") (pintype "passive"))
    )
    (net (code "110") (name "unconnected-(RN3C-1-Pad3)") (class "Default")
      (node (ref "RN3") (pin "3") (pinfunction "1_3") (pintype "passive"))
    )
    (net (code "111") (name "unconnected-(RN3C-2-Pad6)") (class "Default")
      (node (ref "RN3") (pin "6") (pinfunction "2_6") (pintype "passive"))
    )
  )
)
